# boardv2.net
KiCad netlist of a schematic drawn in EAGLE
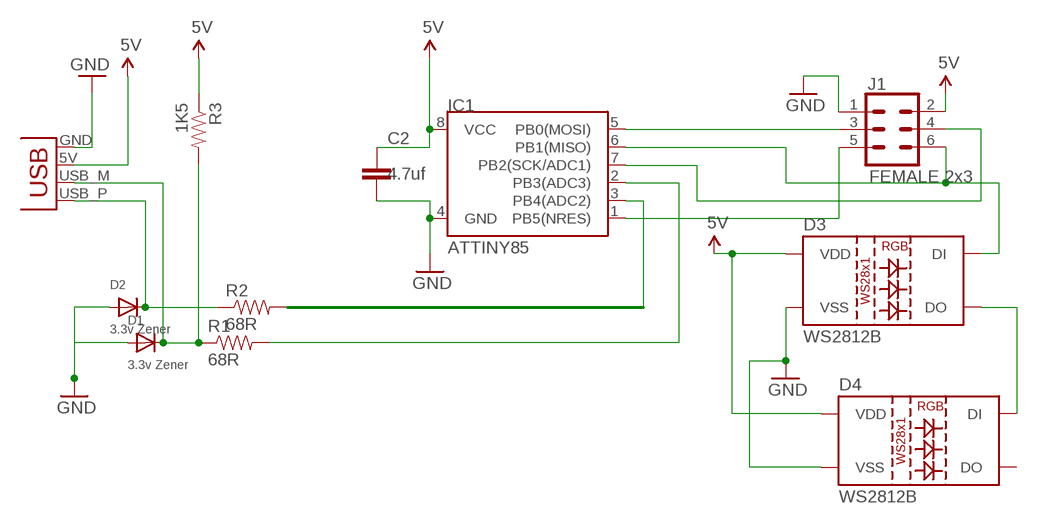
[diagram p0: schematic, sheet 1]

(export (version "E")
  (design (tool "Eeschema 10.0.6"))
  (components
    (comp (ref "C2")
      (value "4.7uf")
      (footprint "eagle-import:C1206")
      (libsource (lib "eagle-import") (part "C-EUC1206"))
    )
    (comp (ref "D1")
      (value "3.3v Zener")
      (footprint "eagle-import:SOD-123")
      (libsource (lib "eagle-import") (part "DIODESOD-123"))
    )
    (comp (ref "D2")
      (value "3.3v Zener")
      (footprint "eagle-import:SOD-123")
      (libsource (lib "eagle-import") (part "DIODESOD-123"))
    )
    (comp (ref "D3")
      (value "WS2812B")
      (footprint "eagle-import:WS2812B")
      (libsource (lib "eagle-import") (part "WS2812B"))
    )
    (comp (ref "D4")
      (value "WS2812B")
      (footprint "eagle-import:WS2812B")
      (libsource (lib "eagle-import") (part "WS2812B"))
    )
    (comp (ref "IC1")
      (value "ATTINY85")
      (footprint "eagle-import:SO08-EIAJ")
      (libsource (lib "eagle-import") (part "ATTINY45"))
    )
    (comp (ref "J1")
      (value "FEMALE 2x3")
      (footprint "eagle-import:2X3")
      (libsource (lib "eagle-import") (part "CONN_03X2FEMALE"))
    )
    (comp (ref "R1")
      (value "68R")
      (footprint "eagle-import:1206")
      (libsource (lib "eagle-import") (part "RESISTOR1206"))
    )
    (comp (ref "R2")
      (value "68R")
      (footprint "eagle-import:1206")
      (libsource (lib "eagle-import") (part "RESISTOR1206"))
    )
    (comp (ref "R3")
      (value "1K5")
      (footprint "eagle-import:1206")
      (libsource (lib "eagle-import") (part "RESISTOR1206"))
    )
    (comp (ref "X1")
      (value "USBPCB")
      (footprint "eagle-import:USB-A-PCB")
      (libsource (lib "eagle-import") (part "USBPCB"))
    )
  )
  (nets
    (net (code "1") (name "5V") (class "Default")
      (node (ref "C2") (pin "1") (pinfunction "1_1") (pintype "passive"))
      (node (ref "D3") (pin "1") (pinfunction "VDD_1") (pintype "bidirectional"))
      (node (ref "D4") (pin "1") (pinfunction "VDD_1") (pintype "bidirectional"))
      (node (ref "IC1") (pin "8") (pinfunction "VCC_8") (pintype "bidirectional"))
      (node (ref "J1") (pin "2") (pinfunction "2_2") (pintype "bidirectional"))
      (node (ref "R3") (pin "1") (pinfunction "1_1") (pintype "passive"))
      (node (ref "X1") (pin "5V") (pinfunction "VBUS_5V") (pintype "bidirectional"))
    )
    (net (code "2") (name "GND") (class "Default")
      (node (ref "C2") (pin "2") (pinfunction "2_2") (pintype "passive"))
      (node (ref "D1") (pin "A") (pinfunction "A_A") (pintype "passive"))
      (node (ref "D2") (pin "A") (pinfunction "A_A") (pintype "passive"))
      (node (ref "D3") (pin "3") (pinfunction "VSS_3") (pintype "bidirectional"))
      (node (ref "D4") (pin "3") (pinfunction "VSS_3") (pintype "bidirectional"))
      (node (ref "IC1") (pin "4") (pinfunction "GND_4") (pintype "bidirectional"))
      (node (ref "J1") (pin "1") (pinfunction "1_1") (pintype "bidirectional"))
      (node (ref "X1") (pin "GND") (pinfunction "GND_GND") (pintype "bidirectional"))
    )
    (net (code "3") (name "Net-(D3-DI)") (class "Default")
      (node (ref "D3") (pin "4") (pinfunction "DI_4") (pintype "bidirectional"))
      (node (ref "IC1") (pin "6") (pinfunction "PB1(MISO)_6") (pintype "bidirectional"))
      (node (ref "J1") (pin "6") (pinfunction "6_6") (pintype "bidirectional"))
    )
    (net (code "4") (name "Net-(D3-DO)") (class "Default")
      (node (ref "D3") (pin "2") (pinfunction "DO_2") (pintype "bidirectional"))
      (node (ref "D4") (pin "4") (pinfunction "DI_4") (pintype "bidirectional"))
    )
    (net (code "5") (name "Net-(IC1-PB0(MOSI))") (class "Default")
      (node (ref "IC1") (pin "5") (pinfunction "PB0(MOSI)_5") (pintype "bidirectional"))
      (node (ref "J1") (pin "3") (pinfunction "3_3") (pintype "bidirectional"))
    )
    (net (code "6") (name "Net-(IC1-PB2(SCK{slash}ADC1))") (class "Default")
      (node (ref "IC1") (pin "7") (pinfunction "PB2(SCK/ADC1)_7") (pintype "bidirectional"))
      (node (ref "J1") (pin "4") (pinfunction "4_4") (pintype "bidirectional"))
    )
    (net (code "7") (name "Net-(IC1-PB3(ADC3))") (class "Default")
      (node (ref "IC1") (pin "2") (pinfunction "PB3(ADC3)_2") (pintype "bidirectional"))
      (node (ref "R1") (pin "2") (pinfunction "2_2") (pintype "passive"))
    )
    (net (code "8") (name "Net-(IC1-PB4(ADC2))") (class "Default")
      (node (ref "IC1") (pin "3") (pinfunction "PB4(ADC2)_3") (pintype "bidirectional"))
      (node (ref "R2") (pin "2") (pinfunction "2_2") (pintype "passive"))
    )
    (net (code "9") (name "Net-(IC1-PB5(NRES))") (class "Default")
      (node (ref "IC1") (pin "1") (pinfunction "PB5(NRES)_1") (pintype "bidirectional"))
      (node (ref "J1") (pin "5") (pinfunction "5_5") (pintype "bidirectional"))
    )
    (net (code "10") (name "Net-(X1-D+)") (class "Default")
      (node (ref "D2") (pin "C") (pinfunction "C_C") (pintype "passive"))
      (node (ref "R2") (pin "1") (pinfunction "1_1") (pintype "passive"))
      (node (ref "X1") (pin "USB_P") (pinfunction "D+_USB_P") (pintype "bidirectional"))
    )
    (net (code "11") (name "Net-(X1-D-)") (class "Default")
      (node (ref "D1") (pin "C") (pinfunction "C_C") (pintype "passive"))
      (node (ref "R1") (pin "1") (pinfunction "1_1") (pintype "passive"))
      (node (ref "R3") (pin "2") (pinfunction "2_2") (pintype "passive"))
      (node (ref "X1") (pin "USB_M") (pinfunction "D-_USB_M") (pintype "bidirectional"))
    )
    (net (code "12") (name "unconnected-(D4-DO-Pad2)") (class "Default")
      (node (ref "D4") (pin "2") (pinfunction "DO_2") (pintype "bidirectional"))
    )
  )
)
